# headerP3_blk.net
KiCad netlist of a schematic drawn in Altium Designer
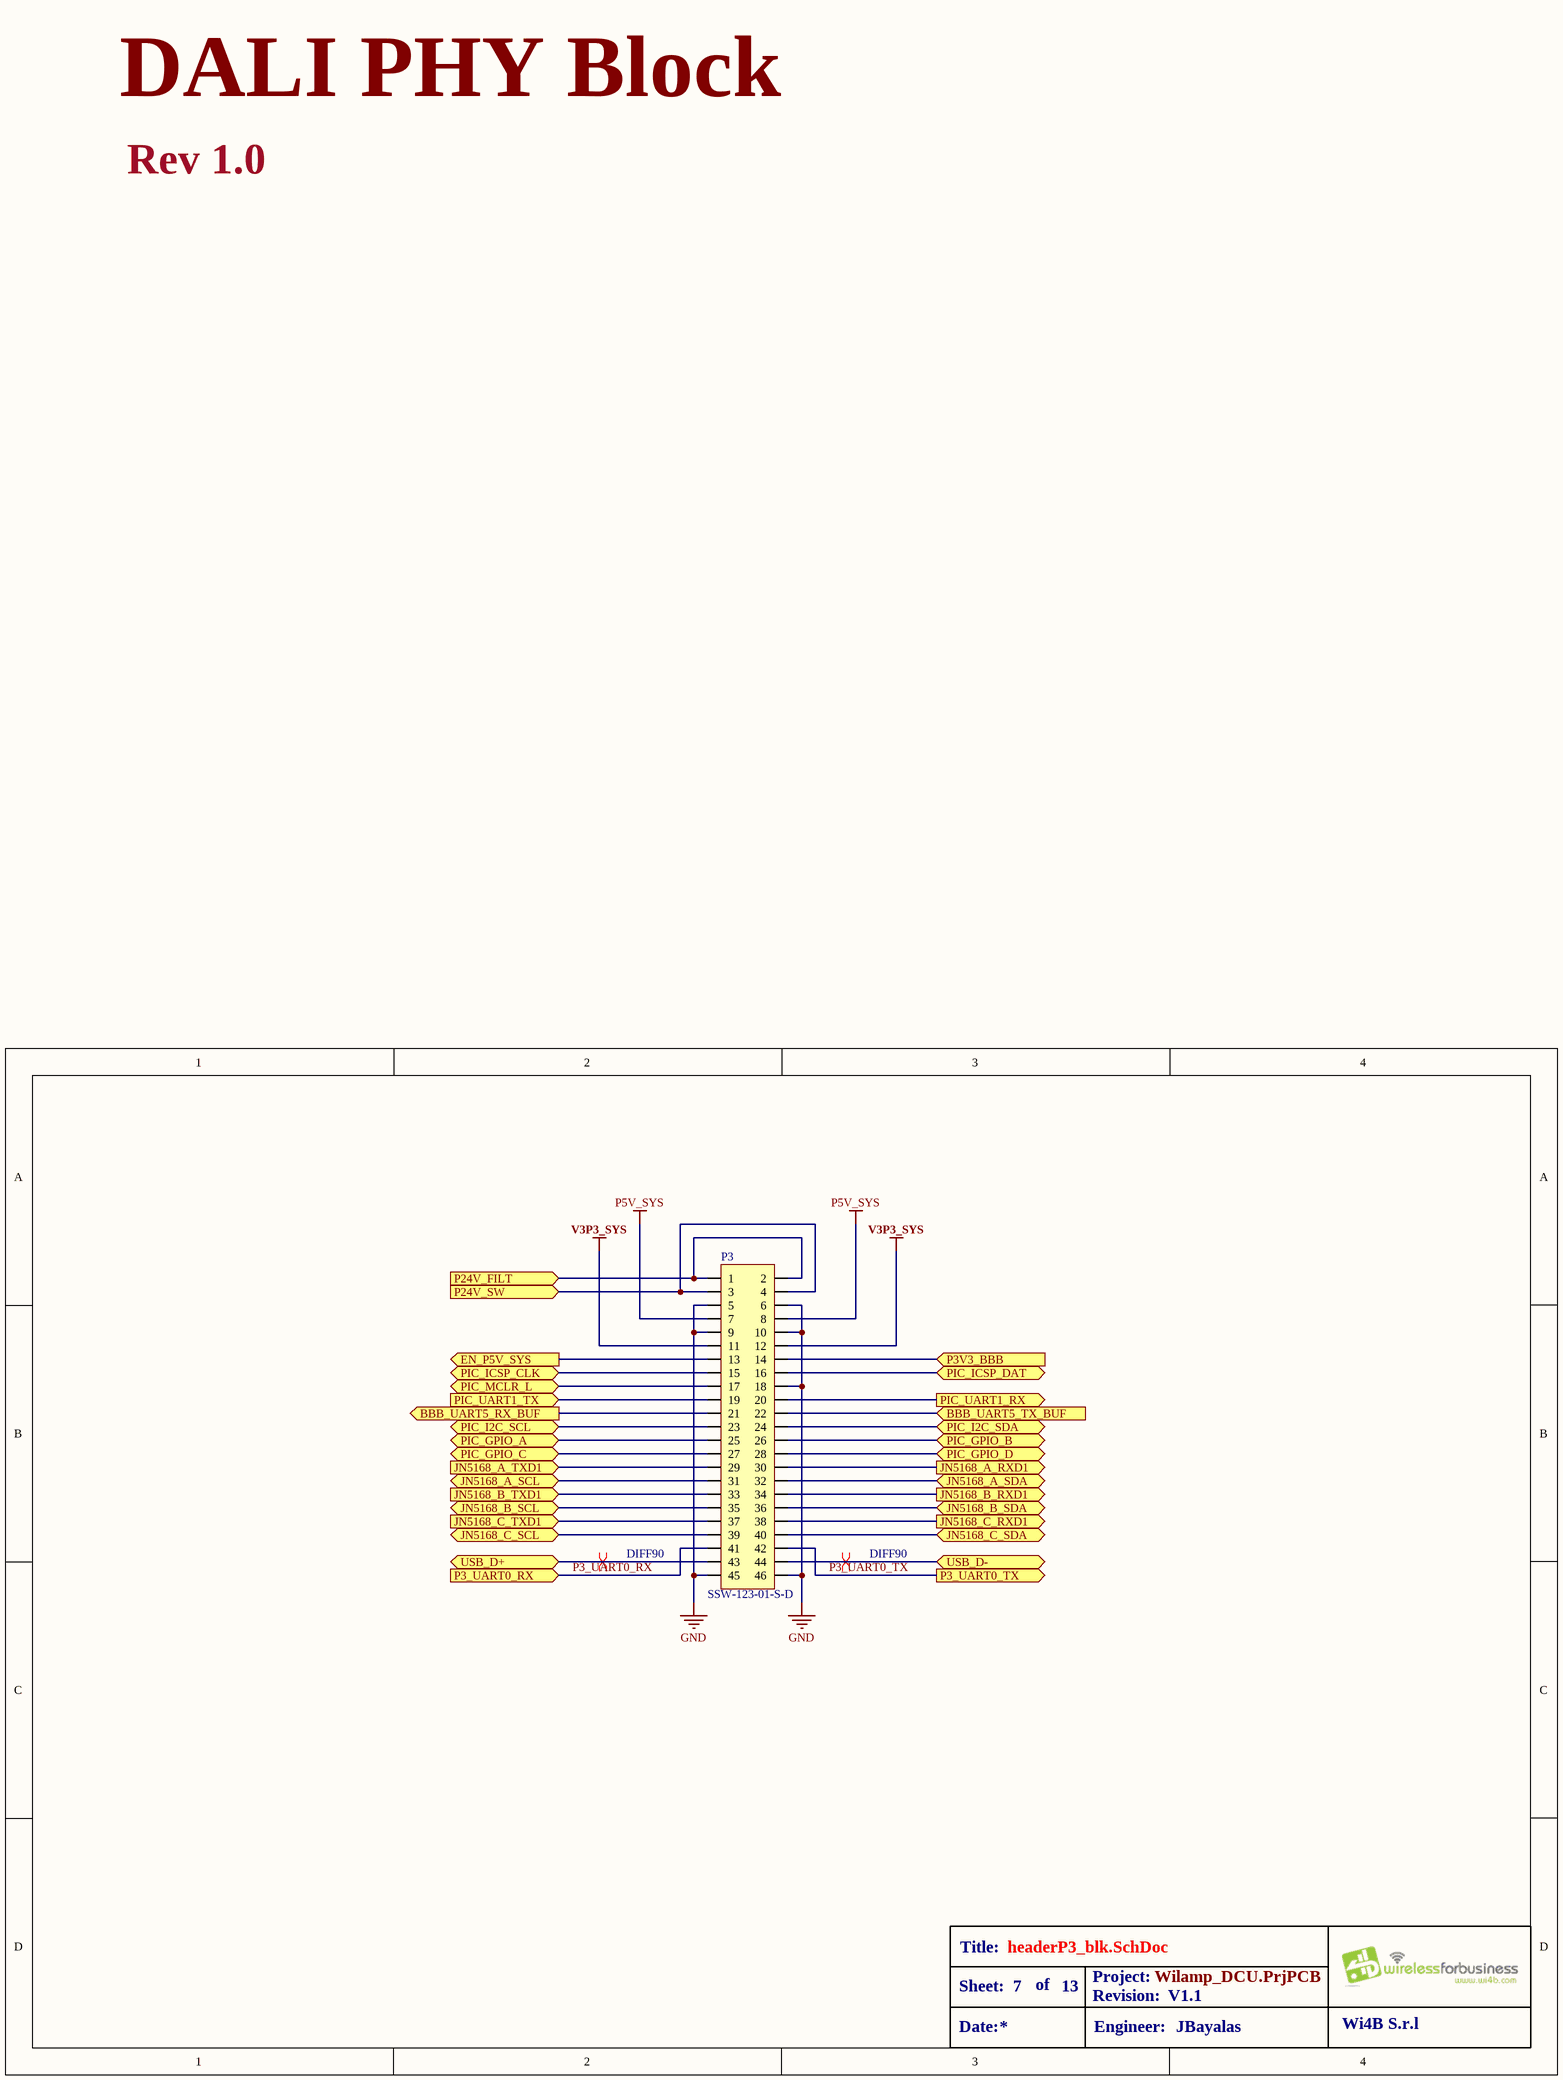
[diagram p0: headerP3_blk.SchDoc]

(export (version "E")
  (design (tool "Eeschema 10.0.6"))
  (components
    (comp (ref "P3")
      (value "SSW-123-01-S-D")
      (footprint "2x23 Header Female")
      (description "CONN RCPT .100\" 46POS DUAL GOLD")
      (libsource (lib "Connector") (part "SSW-123-01-S-D"))
    )
  )
  (nets
    (net (code "1") (name "/BBB_UART5_RX_BUF") (class "Default")
      (node (ref "P3") (pin "21") (pinfunction "21_21") (pintype "passive"))
    )
    (net (code "2") (name "/BBB_UART5_TX_BUF") (class "Default")
      (node (ref "P3") (pin "22") (pinfunction "22_22") (pintype "passive"))
    )
    (net (code "3") (name "/EN_P5V_SYS") (class "Default")
      (node (ref "P3") (pin "13") (pinfunction "13_13") (pintype "passive"))
    )
    (net (code "4") (name "/JN5168_A_RXD1") (class "Default")
      (node (ref "P3") (pin "30") (pinfunction "30_30") (pintype "passive"))
    )
    (net (code "5") (name "/JN5168_A_SCL") (class "Default")
      (node (ref "P3") (pin "31") (pinfunction "31_31") (pintype "passive"))
    )
    (net (code "6") (name "/JN5168_A_SDA") (class "Default")
      (node (ref "P3") (pin "32") (pinfunction "32_32") (pintype "passive"))
    )
    (net (code "7") (name "/JN5168_A_TXD1") (class "Default")
      (node (ref "P3") (pin "29") (pinfunction "29_29") (pintype "passive"))
    )
    (net (code "8") (name "/JN5168_B_RXD1") (class "Default")
      (node (ref "P3") (pin "34") (pinfunction "34_34") (pintype "passive"))
    )
    (net (code "9") (name "/JN5168_B_SCL") (class "Default")
      (node (ref "P3") (pin "35") (pinfunction "35_35") (pintype "passive"))
    )
    (net (code "10") (name "/JN5168_B_SDA") (class "Default")
      (node (ref "P3") (pin "36") (pinfunction "36_36") (pintype "passive"))
    )
    (net (code "11") (name "/JN5168_B_TXD1") (class "Default")
      (node (ref "P3") (pin "33") (pinfunction "33_33") (pintype "passive"))
    )
    (net (code "12") (name "/JN5168_C_RXD1") (class "Default")
      (node (ref "P3") (pin "38") (pinfunction "38_38") (pintype "passive"))
    )
    (net (code "13") (name "/JN5168_C_SCL") (class "Default")
      (node (ref "P3") (pin "39") (pinfunction "39_39") (pintype "passive"))
    )
    (net (code "14") (name "/JN5168_C_SDA") (class "Default")
      (node (ref "P3") (pin "40") (pinfunction "40_40") (pintype "passive"))
    )
    (net (code "15") (name "/JN5168_C_TXD1") (class "Default")
      (node (ref "P3") (pin "37") (pinfunction "37_37") (pintype "passive"))
    )
    (net (code "16") (name "/P3V3_BBB") (class "Default")
      (node (ref "P3") (pin "14") (pinfunction "14_14") (pintype "passive"))
    )
    (net (code "17") (name "/P3_UART0_RX") (class "Default")
      (node (ref "P3") (pin "41") (pinfunction "41_41") (pintype "passive"))
    )
    (net (code "18") (name "/P3_UART0_TX") (class "Default")
      (node (ref "P3") (pin "42") (pinfunction "42_42") (pintype "passive"))
    )
    (net (code "19") (name "/P24V_FILT") (class "Default")
      (node (ref "P3") (pin "1") (pinfunction "1_1") (pintype "passive"))
      (node (ref "P3") (pin "2") (pinfunction "2_2") (pintype "passive"))
    )
    (net (code "20") (name "/P24V_SW") (class "Default")
      (node (ref "P3") (pin "3") (pinfunction "3_3") (pintype "passive"))
      (node (ref "P3") (pin "4") (pinfunction "4_4") (pintype "passive"))
    )
    (net (code "21") (name "/PIC_GPIO_A") (class "Default")
      (node (ref "P3") (pin "25") (pinfunction "25_25") (pintype "passive"))
    )
    (net (code "22") (name "/PIC_GPIO_B") (class "Default")
      (node (ref "P3") (pin "26") (pinfunction "26_26") (pintype "passive"))
    )
    (net (code "23") (name "/PIC_GPIO_C") (class "Default")
      (node (ref "P3") (pin "27") (pinfunction "27_27") (pintype "passive"))
    )
    (net (code "24") (name "/PIC_GPIO_D") (class "Default")
      (node (ref "P3") (pin "28") (pinfunction "28_28") (pintype "passive"))
    )
    (net (code "25") (name "/PIC_I2C_SCL") (class "Default")
      (node (ref "P3") (pin "23") (pinfunction "23_23") (pintype "passive"))
    )
    (net (code "26") (name "/PIC_I2C_SDA") (class "Default")
      (node (ref "P3") (pin "24") (pinfunction "24_24") (pintype "passive"))
    )
    (net (code "27") (name "/PIC_ICSP_CLK") (class "Default")
      (node (ref "P3") (pin "15") (pinfunction "15_15") (pintype "passive"))
    )
    (net (code "28") (name "/PIC_ICSP_DAT") (class "Default")
      (node (ref "P3") (pin "16") (pinfunction "16_16") (pintype "passive"))
    )
    (net (code "29") (name "/PIC_MCLR_L") (class "Default")
      (node (ref "P3") (pin "17") (pinfunction "17_17") (pintype "passive"))
    )
    (net (code "30") (name "/PIC_UART1_RX") (class "Default")
      (node (ref "P3") (pin "20") (pinfunction "20_20") (pintype "passive"))
    )
    (net (code "31") (name "/PIC_UART1_TX") (class "Default")
      (node (ref "P3") (pin "19") (pinfunction "19_19") (pintype "passive"))
    )
    (net (code "32") (name "/USB_D+") (class "Default")
      (node (ref "P3") (pin "43") (pinfunction "43_43") (pintype "passive"))
    )
    (net (code "33") (name "/USB_D-") (class "Default")
      (node (ref "P3") (pin "44") (pinfunction "44_44") (pintype "passive"))
    )
    (net (code "34") (name "GND") (class "Default")
      (node (ref "P3") (pin "10") (pinfunction "10_10") (pintype "passive"))
      (node (ref "P3") (pin "18") (pinfunction "18_18") (pintype "passive"))
      (node (ref "P3") (pin "45") (pinfunction "45_45") (pintype "passive"))
      (node (ref "P3") (pin "46") (pinfunction "46_46") (pintype "passive"))
      (node (ref "P3") (pin "5") (pinfunction "5_5") (pintype "passive"))
      (node (ref "P3") (pin "6") (pinfunction "6_6") (pintype "passive"))
      (node (ref "P3") (pin "9") (pinfunction "9_9") (pintype "passive"))
    )
    (net (code "35") (name "P5V_SYS") (class "Default")
      (node (ref "P3") (pin "7") (pinfunction "7_7") (pintype "passive"))
      (node (ref "P3") (pin "8") (pinfunction "8_8") (pintype "passive"))
    )
    (net (code "36") (name "V3P3_SYS") (class "Default")
      (node (ref "P3") (pin "11") (pinfunction "11_11") (pintype "passive"))
      (node (ref "P3") (pin "12") (pinfunction "12_12") (pintype "passive"))
    )
  )
)
